# Sheet1.net
KiCad netlist of a schematic drawn in Altium Designer
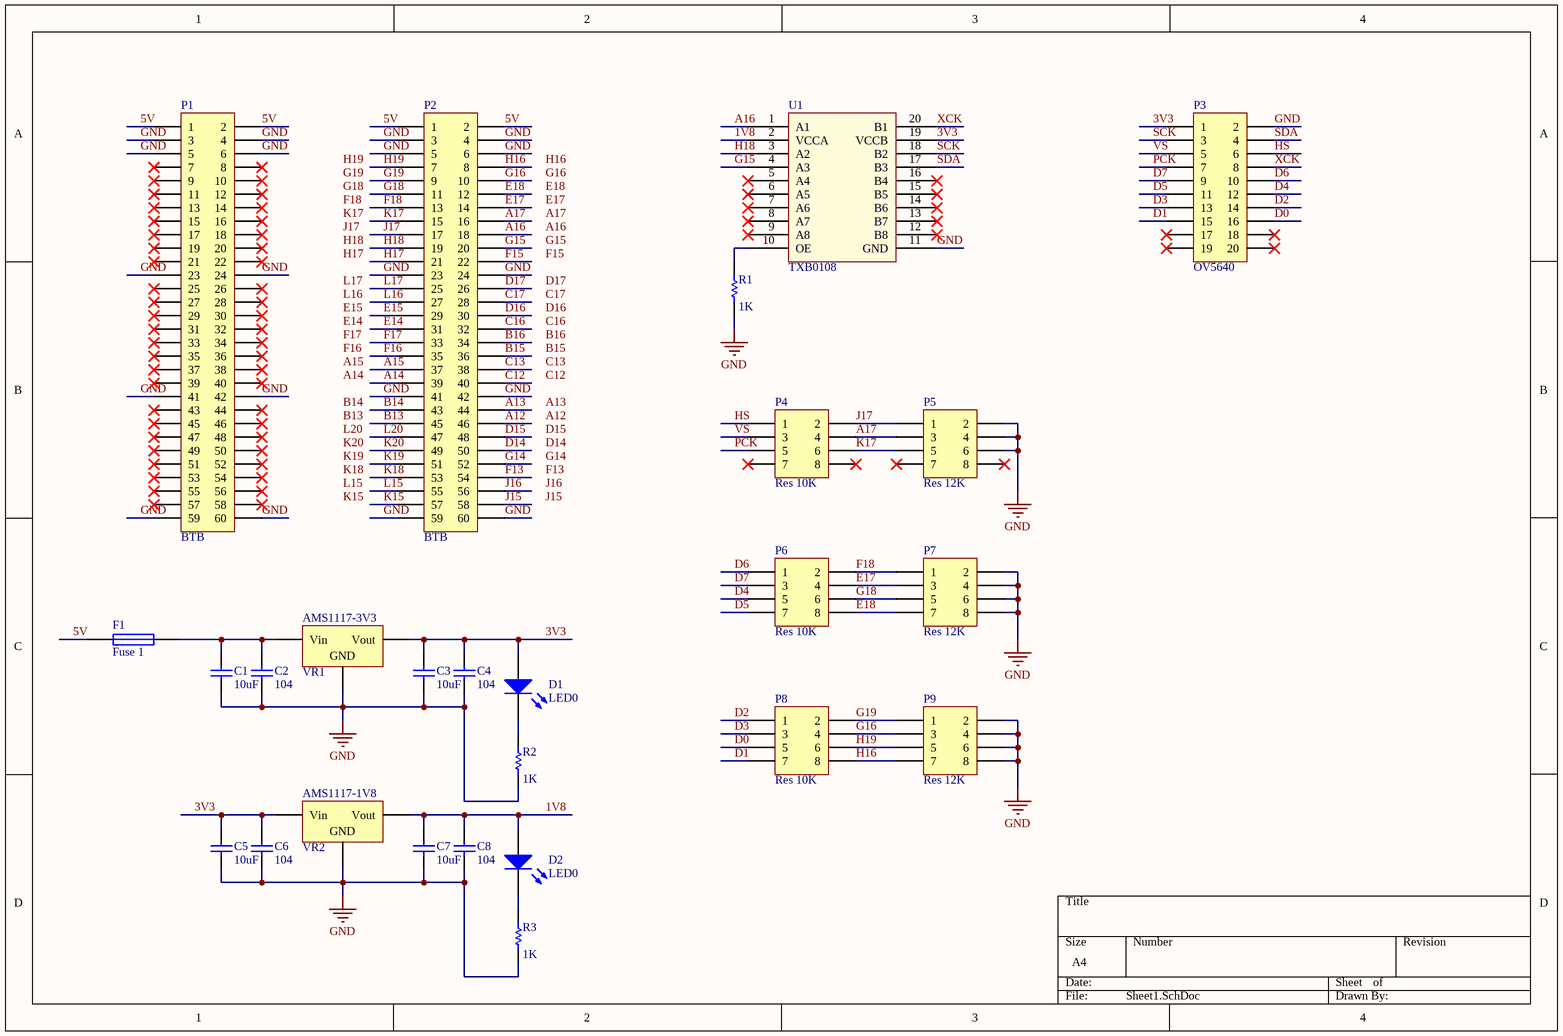
[diagram p0: Sheet1.SchDoc]

(export (version "E")
  (design (tool "Eeschema 10.0.6"))
  (components
    (comp (ref "C1")
      (value "10uF")
      (footprint "R0805")
      (description "Capacitor")
      (fields (field (name "Comment") "Cap") (field (name "PUBLISHER") "Altium Limited"))
      (libsource (lib "Miscellaneous Devices") (part "Cap"))
    )
    (comp (ref "C2")
      (value "104")
      (footprint "R0805")
      (description "Capacitor")
      (fields (field (name "Comment") "Cap") (field (name "PUBLISHER") "Altium Limited"))
      (libsource (lib "Miscellaneous Devices") (part "Cap"))
    )
    (comp (ref "C3")
      (value "10uF")
      (footprint "R0805")
      (description "Capacitor")
      (fields (field (name "Comment") "Cap") (field (name "PUBLISHER") "Altium Limited"))
      (libsource (lib "Miscellaneous Devices") (part "Cap"))
    )
    (comp (ref "C4")
      (value "104")
      (footprint "R0805")
      (description "Capacitor")
      (fields (field (name "Comment") "Cap") (field (name "PUBLISHER") "Altium Limited"))
      (libsource (lib "Miscellaneous Devices") (part "Cap"))
    )
    (comp (ref "C5")
      (value "10uF")
      (footprint "R0805")
      (description "Capacitor")
      (fields (field (name "Comment") "Cap") (field (name "PUBLISHER") "Altium Limited"))
      (libsource (lib "Miscellaneous Devices") (part "Cap"))
    )
    (comp (ref "C6")
      (value "104")
      (footprint "R0805")
      (description "Capacitor")
      (fields (field (name "Comment") "Cap") (field (name "PUBLISHER") "Altium Limited"))
      (libsource (lib "Miscellaneous Devices") (part "Cap"))
    )
    (comp (ref "C7")
      (value "10uF")
      (footprint "R0805")
      (description "Capacitor")
      (fields (field (name "Comment") "Cap") (field (name "PUBLISHER") "Altium Limited"))
      (libsource (lib "Miscellaneous Devices") (part "Cap"))
    )
    (comp (ref "C8")
      (value "104")
      (footprint "R0805")
      (description "Capacitor")
      (fields (field (name "Comment") "Cap") (field (name "PUBLISHER") "Altium Limited"))
      (libsource (lib "Miscellaneous Devices") (part "Cap"))
    )
    (comp (ref "D1")
      (value "LED0")
      (footprint "LED0805红")
      (description "Typical INFRARED GaAs LED")
      (fields (field (name "PUBLISHER") "Altium Limited"))
      (libsource (lib "Miscellaneous Devices") (part "LED0"))
    )
    (comp (ref "D2")
      (value "LED0")
      (footprint "LED0805红")
      (description "Typical INFRARED GaAs LED")
      (fields (field (name "PUBLISHER") "Altium Limited"))
      (libsource (lib "Miscellaneous Devices") (part "LED0"))
    )
    (comp (ref "F1")
      (value "Fuse 1")
      (footprint "R0805")
      (description "Fuse")
      (fields (field (name "PUBLISHER") "Altium Limited"))
      (libsource (lib "Miscellaneous Devices") (part "Fuse 1"))
    )
    (comp (ref "P1")
      (value "BTB")
      (footprint "BTBCON_0.8mm_60P")
      (description "Header, 30-Pin, Dual row")
      (fields (field (name "PUBLISHER") "Altium Limited"))
      (libsource (lib "Miscellaneous Connectors") (part "Header 30X2"))
    )
    (comp (ref "P2")
      (value "BTB")
      (footprint "BTBCON_0.8mm_60P")
      (description "Header, 30-Pin, Dual row")
      (fields (field (name "PUBLISHER") "Altium Limited"))
      (libsource (lib "Miscellaneous Connectors") (part "Header 30X2"))
    )
    (comp (ref "P3")
      (value "OV5640")
      (footprint "HDR2X10")
      (description "Header, 10-Pin, Dual row")
      (fields (field (name "PUBLISHER") "Altium Limited"))
      (libsource (lib "Miscellaneous Connectors") (part "Header 10X2"))
    )
    (comp (ref "P4")
      (value "Res 10K")
      (footprint "排阻(4位贴片)")
      (description "Header, 4-Pin, Dual row")
      (fields (field (name "PUBLISHER") "Altium Limited"))
      (libsource (lib "Miscellaneous Connectors") (part "Header 4X2"))
    )
    (comp (ref "P5")
      (value "Res 12K")
      (footprint "排阻(4位贴片)")
      (description "Header, 4-Pin, Dual row")
      (fields (field (name "PUBLISHER") "Altium Limited"))
      (libsource (lib "Miscellaneous Connectors") (part "Header 4X2"))
    )
    (comp (ref "P6")
      (value "Res 10K")
      (footprint "排阻(4位贴片)")
      (description "Header, 4-Pin, Dual row")
      (fields (field (name "PUBLISHER") "Altium Limited"))
      (libsource (lib "Miscellaneous Connectors") (part "Header 4X2"))
    )
    (comp (ref "P7")
      (value "Res 12K")
      (footprint "排阻(4位贴片)")
      (description "Header, 4-Pin, Dual row")
      (fields (field (name "PUBLISHER") "Altium Limited"))
      (libsource (lib "Miscellaneous Connectors") (part "Header 4X2"))
    )
    (comp (ref "P8")
      (value "Res 10K")
      (footprint "排阻(4位贴片)")
      (description "Header, 4-Pin, Dual row")
      (fields (field (name "PUBLISHER") "Altium Limited"))
      (libsource (lib "Miscellaneous Connectors") (part "Header 4X2"))
    )
    (comp (ref "P9")
      (value "Res 12K")
      (footprint "排阻(4位贴片)")
      (description "Header, 4-Pin, Dual row")
      (fields (field (name "PUBLISHER") "Altium Limited"))
      (libsource (lib "Miscellaneous Connectors") (part "Header 4X2"))
    )
    (comp (ref "R1")
      (value "1K")
      (footprint "R0805")
      (description "Semiconductor Resistor")
      (fields (field (name "Comment") "Res Semi") (field (name "PUBLISHER") "Altium Limited"))
      (libsource (lib "Miscellaneous Devices") (part "Res Semi"))
    )
    (comp (ref "R2")
      (value "1K")
      (footprint "R0805")
      (description "Resistor")
      (fields (field (name "Comment") "Res1") (field (name "PUBLISHER") "Altium Limited"))
      (libsource (lib "Miscellaneous Devices") (part "Res1"))
    )
    (comp (ref "R3")
      (value "1K")
      (footprint "R0805")
      (description "Resistor")
      (fields (field (name "Comment") "Res1") (field (name "PUBLISHER") "Altium Limited"))
      (libsource (lib "Miscellaneous Devices") (part "Res1"))
    )
    (comp (ref "U1") (value "TXB0108") (footprint "TXB0108") (libsource (lib "TXB0108") (part "TXB0108")))
    (comp (ref "VR1")
      (value "AMS1117-3V3")
      (footprint "AMS1117")
      (description "Voltage Regulator")
      (fields (field (name "PUBLISHER") "Altium Limited"))
      (libsource (lib "Miscellaneous Devices") (part "Volt Reg"))
    )
    (comp (ref "VR2")
      (value "AMS1117-1V8")
      (footprint "AMS1117")
      (description "Voltage Regulator")
      (fields (field (name "PUBLISHER") "Altium Limited"))
      (libsource (lib "Miscellaneous Devices") (part "Volt Reg"))
    )
  )
  (nets
    (net (code "1") (name "/1V8") (class "Default")
      (node (ref "C7") (pin "2") (pinfunction "2_2") (pintype "passive"))
      (node (ref "C8") (pin "2") (pinfunction "2_2") (pintype "passive"))
      (node (ref "D2") (pin "1") (pinfunction "A_1") (pintype "passive"))
      (node (ref "U1") (pin "2") (pinfunction "VCCA_2") (pintype "passive"))
      (node (ref "VR2") (pin "2") (pinfunction "Vout_2") (pintype "passive"))
    )
    (net (code "2") (name "/3V3") (class "Default")
      (node (ref "C3") (pin "2") (pinfunction "2_2") (pintype "passive"))
      (node (ref "C4") (pin "2") (pinfunction "2_2") (pintype "passive"))
      (node (ref "C5") (pin "2") (pinfunction "2_2") (pintype "passive"))
      (node (ref "C6") (pin "2") (pinfunction "2_2") (pintype "passive"))
      (node (ref "D1") (pin "1") (pinfunction "A_1") (pintype "passive"))
      (node (ref "P3") (pin "1") (pinfunction "1_1") (pintype "passive"))
      (node (ref "U1") (pin "19") (pinfunction "VCCB_19") (pintype "passive"))
      (node (ref "VR1") (pin "2") (pinfunction "Vout_2") (pintype "passive"))
      (node (ref "VR2") (pin "3") (pinfunction "Vin_3") (pintype "passive"))
    )
    (net (code "3") (name "/5V") (class "Default")
      (node (ref "F1") (pin "1") (pinfunction "1_1") (pintype "passive"))
      (node (ref "P1") (pin "1") (pinfunction "1_1") (pintype "passive"))
      (node (ref "P1") (pin "2") (pinfunction "2_2") (pintype "passive"))
      (node (ref "P2") (pin "1") (pinfunction "1_1") (pintype "passive"))
      (node (ref "P2") (pin "2") (pinfunction "2_2") (pintype "passive"))
    )
    (net (code "4") (name "/A12") (class "Default")
      (node (ref "P2") (pin "46") (pinfunction "46_46") (pintype "passive"))
    )
    (net (code "5") (name "/A13") (class "Default")
      (node (ref "P2") (pin "44") (pinfunction "44_44") (pintype "passive"))
    )
    (net (code "6") (name "/A14") (class "Default")
      (node (ref "P2") (pin "39") (pinfunction "39_39") (pintype "passive"))
    )
    (net (code "7") (name "/A15") (class "Default")
      (node (ref "P2") (pin "37") (pinfunction "37_37") (pintype "passive"))
    )
    (net (code "8") (name "/A16") (class "Default")
      (node (ref "P2") (pin "18") (pinfunction "18_18") (pintype "passive"))
      (node (ref "U1") (pin "1") (pinfunction "A1_1") (pintype "passive"))
    )
    (net (code "9") (name "/A17") (class "Default")
      (node (ref "P2") (pin "16") (pinfunction "16_16") (pintype "passive"))
      (node (ref "P4") (pin "4") (pinfunction "4_4") (pintype "passive"))
      (node (ref "P5") (pin "3") (pinfunction "3_3") (pintype "passive"))
    )
    (net (code "10") (name "/B13") (class "Default")
      (node (ref "P2") (pin "45") (pinfunction "45_45") (pintype "passive"))
    )
    (net (code "11") (name "/B14") (class "Default")
      (node (ref "P2") (pin "43") (pinfunction "43_43") (pintype "passive"))
    )
    (net (code "12") (name "/B15") (class "Default")
      (node (ref "P2") (pin "36") (pinfunction "36_36") (pintype "passive"))
    )
    (net (code "13") (name "/B16") (class "Default")
      (node (ref "P2") (pin "34") (pinfunction "34_34") (pintype "passive"))
    )
    (net (code "14") (name "/C12") (class "Default")
      (node (ref "P2") (pin "40") (pinfunction "40_40") (pintype "passive"))
    )
    (net (code "15") (name "/C13") (class "Default")
      (node (ref "P2") (pin "38") (pinfunction "38_38") (pintype "passive"))
    )
    (net (code "16") (name "/C16") (class "Default")
      (node (ref "P2") (pin "32") (pinfunction "32_32") (pintype "passive"))
    )
    (net (code "17") (name "/C17") (class "Default")
      (node (ref "P2") (pin "28") (pinfunction "28_28") (pintype "passive"))
    )
    (net (code "18") (name "/D0") (class "Default")
      (node (ref "P3") (pin "16") (pinfunction "16_16") (pintype "passive"))
      (node (ref "P8") (pin "5") (pinfunction "5_5") (pintype "passive"))
    )
    (net (code "19") (name "/D1") (class "Default")
      (node (ref "P3") (pin "15") (pinfunction "15_15") (pintype "passive"))
      (node (ref "P8") (pin "7") (pinfunction "7_7") (pintype "passive"))
    )
    (net (code "20") (name "/D2") (class "Default")
      (node (ref "P3") (pin "14") (pinfunction "14_14") (pintype "passive"))
      (node (ref "P8") (pin "1") (pinfunction "1_1") (pintype "passive"))
    )
    (net (code "21") (name "/D3") (class "Default")
      (node (ref "P3") (pin "13") (pinfunction "13_13") (pintype "passive"))
      (node (ref "P8") (pin "3") (pinfunction "3_3") (pintype "passive"))
    )
    (net (code "22") (name "/D4") (class "Default")
      (node (ref "P3") (pin "12") (pinfunction "12_12") (pintype "passive"))
      (node (ref "P6") (pin "5") (pinfunction "5_5") (pintype "passive"))
    )
    (net (code "23") (name "/D5") (class "Default")
      (node (ref "P3") (pin "11") (pinfunction "11_11") (pintype "passive"))
      (node (ref "P6") (pin "7") (pinfunction "7_7") (pintype "passive"))
    )
    (net (code "24") (name "/D6") (class "Default")
      (node (ref "P3") (pin "10") (pinfunction "10_10") (pintype "passive"))
      (node (ref "P6") (pin "1") (pinfunction "1_1") (pintype "passive"))
    )
    (net (code "25") (name "/D7") (class "Default")
      (node (ref "P3") (pin "9") (pinfunction "9_9") (pintype "passive"))
      (node (ref "P6") (pin "3") (pinfunction "3_3") (pintype "passive"))
    )
    (net (code "26") (name "/D14") (class "Default")
      (node (ref "P2") (pin "50") (pinfunction "50_50") (pintype "passive"))
    )
    (net (code "27") (name "/D15") (class "Default")
      (node (ref "P2") (pin "48") (pinfunction "48_48") (pintype "passive"))
    )
    (net (code "28") (name "/D16") (class "Default")
      (node (ref "P2") (pin "30") (pinfunction "30_30") (pintype "passive"))
    )
    (net (code "29") (name "/D17") (class "Default")
      (node (ref "P2") (pin "26") (pinfunction "26_26") (pintype "passive"))
    )
    (net (code "30") (name "/E14") (class "Default")
      (node (ref "P2") (pin "31") (pinfunction "31_31") (pintype "passive"))
    )
    (net (code "31") (name "/E15") (class "Default")
      (node (ref "P2") (pin "29") (pinfunction "29_29") (pintype "passive"))
    )
    (net (code "32") (name "/E17") (class "Default")
      (node (ref "P2") (pin "14") (pinfunction "14_14") (pintype "passive"))
      (node (ref "P6") (pin "4") (pinfunction "4_4") (pintype "passive"))
      (node (ref "P7") (pin "3") (pinfunction "3_3") (pintype "passive"))
    )
    (net (code "33") (name "/E18") (class "Default")
      (node (ref "P2") (pin "12") (pinfunction "12_12") (pintype "passive"))
      (node (ref "P6") (pin "8") (pinfunction "8_8") (pintype "passive"))
      (node (ref "P7") (pin "7") (pinfunction "7_7") (pintype "passive"))
    )
    (net (code "34") (name "/F13") (class "Default")
      (node (ref "P2") (pin "54") (pinfunction "54_54") (pintype "passive"))
    )
    (net (code "35") (name "/F15") (class "Default")
      (node (ref "P2") (pin "22") (pinfunction "22_22") (pintype "passive"))
    )
    (net (code "36") (name "/F16") (class "Default")
      (node (ref "P2") (pin "35") (pinfunction "35_35") (pintype "passive"))
    )
    (net (code "37") (name "/F17") (class "Default")
      (node (ref "P2") (pin "33") (pinfunction "33_33") (pintype "passive"))
    )
    (net (code "38") (name "/F18") (class "Default")
      (node (ref "P2") (pin "13") (pinfunction "13_13") (pintype "passive"))
      (node (ref "P6") (pin "2") (pinfunction "2_2") (pintype "passive"))
      (node (ref "P7") (pin "1") (pinfunction "1_1") (pintype "passive"))
    )
    (net (code "39") (name "/G14") (class "Default")
      (node (ref "P2") (pin "52") (pinfunction "52_52") (pintype "passive"))
    )
    (net (code "40") (name "/G15") (class "Default")
      (node (ref "P2") (pin "20") (pinfunction "20_20") (pintype "passive"))
      (node (ref "U1") (pin "4") (pinfunction "A3_4") (pintype "passive"))
    )
    (net (code "41") (name "/G16") (class "Default")
      (node (ref "P2") (pin "10") (pinfunction "10_10") (pintype "passive"))
      (node (ref "P8") (pin "4") (pinfunction "4_4") (pintype "passive"))
      (node (ref "P9") (pin "3") (pinfunction "3_3") (pintype "passive"))
    )
    (net (code "42") (name "/G18") (class "Default")
      (node (ref "P2") (pin "11") (pinfunction "11_11") (pintype "passive"))
      (node (ref "P6") (pin "6") (pinfunction "6_6") (pintype "passive"))
      (node (ref "P7") (pin "5") (pinfunction "5_5") (pintype "passive"))
    )
    (net (code "43") (name "/G19") (class "Default")
      (node (ref "P2") (pin "9") (pinfunction "9_9") (pintype "passive"))
      (node (ref "P8") (pin "2") (pinfunction "2_2") (pintype "passive"))
      (node (ref "P9") (pin "1") (pinfunction "1_1") (pintype "passive"))
    )
    (net (code "44") (name "/H16") (class "Default")
      (node (ref "P2") (pin "8") (pinfunction "8_8") (pintype "passive"))
      (node (ref "P8") (pin "8") (pinfunction "8_8") (pintype "passive"))
      (node (ref "P9") (pin "7") (pinfunction "7_7") (pintype "passive"))
    )
    (net (code "45") (name "/H17") (class "Default")
      (node (ref "P2") (pin "21") (pinfunction "21_21") (pintype "passive"))
    )
    (net (code "46") (name "/H18") (class "Default")
      (node (ref "P2") (pin "19") (pinfunction "19_19") (pintype "passive"))
      (node (ref "U1") (pin "3") (pinfunction "A2_3") (pintype "passive"))
    )
    (net (code "47") (name "/H19") (class "Default")
      (node (ref "P2") (pin "7") (pinfunction "7_7") (pintype "passive"))
      (node (ref "P8") (pin "6") (pinfunction "6_6") (pintype "passive"))
      (node (ref "P9") (pin "5") (pinfunction "5_5") (pintype "passive"))
    )
    (net (code "48") (name "/HS") (class "Default")
      (node (ref "P3") (pin "6") (pinfunction "6_6") (pintype "passive"))
      (node (ref "P4") (pin "1") (pinfunction "1_1") (pintype "passive"))
    )
    (net (code "49") (name "/J15") (class "Default")
      (node (ref "P2") (pin "58") (pinfunction "58_58") (pintype "passive"))
    )
    (net (code "50") (name "/J16") (class "Default")
      (node (ref "P2") (pin "56") (pinfunction "56_56") (pintype "passive"))
    )
    (net (code "51") (name "/J17") (class "Default")
      (node (ref "P2") (pin "17") (pinfunction "17_17") (pintype "passive"))
      (node (ref "P4") (pin "2") (pinfunction "2_2") (pintype "passive"))
      (node (ref "P5") (pin "1") (pinfunction "1_1") (pintype "passive"))
    )
    (net (code "52") (name "/K15") (class "Default")
      (node (ref "P2") (pin "57") (pinfunction "57_57") (pintype "passive"))
    )
    (net (code "53") (name "/K17") (class "Default")
      (node (ref "P2") (pin "15") (pinfunction "15_15") (pintype "passive"))
      (node (ref "P4") (pin "6") (pinfunction "6_6") (pintype "passive"))
      (node (ref "P5") (pin "5") (pinfunction "5_5") (pintype "passive"))
    )
    (net (code "54") (name "/K18") (class "Default")
      (node (ref "P2") (pin "53") (pinfunction "53_53") (pintype "passive"))
    )
    (net (code "55") (name "/K19") (class "Default")
      (node (ref "P2") (pin "51") (pinfunction "51_51") (pintype "passive"))
    )
    (net (code "56") (name "/K20") (class "Default")
      (node (ref "P2") (pin "49") (pinfunction "49_49") (pintype "passive"))
    )
    (net (code "57") (name "/L15") (class "Default")
      (node (ref "P2") (pin "55") (pinfunction "55_55") (pintype "passive"))
    )
    (net (code "58") (name "/L16") (class "Default")
      (node (ref "P2") (pin "27") (pinfunction "27_27") (pintype "passive"))
    )
    (net (code "59") (name "/L17") (class "Default")
      (node (ref "P2") (pin "25") (pinfunction "25_25") (pintype "passive"))
    )
    (net (code "60") (name "/L20") (class "Default")
      (node (ref "P2") (pin "47") (pinfunction "47_47") (pintype "passive"))
    )
    (net (code "61") (name "/PCK") (class "Default")
      (node (ref "P3") (pin "7") (pinfunction "7_7") (pintype "passive"))
      (node (ref "P4") (pin "5") (pinfunction "5_5") (pintype "passive"))
    )
    (net (code "62") (name "/SCK") (class "Default")
      (node (ref "P3") (pin "3") (pinfunction "3_3") (pintype "passive"))
      (node (ref "U1") (pin "18") (pinfunction "B2_18") (pintype "passive"))
    )
    (net (code "63") (name "/SDA") (class "Default")
      (node (ref "P3") (pin "4") (pinfunction "4_4") (pintype "passive"))
      (node (ref "U1") (pin "17") (pinfunction "B3_17") (pintype "passive"))
    )
    (net (code "64") (name "/VS") (class "Default")
      (node (ref "P3") (pin "5") (pinfunction "5_5") (pintype "passive"))
      (node (ref "P4") (pin "3") (pinfunction "3_3") (pintype "passive"))
    )
    (net (code "65") (name "/XCK") (class "Default")
      (node (ref "P3") (pin "8") (pinfunction "8_8") (pintype "passive"))
      (node (ref "U1") (pin "20") (pinfunction "B1_20") (pintype "passive"))
    )
    (net (code "66") (name "GND") (class "Default")
      (node (ref "C1") (pin "1") (pinfunction "1_1") (pintype "passive"))
      (node (ref "C2") (pin "1") (pinfunction "1_1") (pintype "passive"))
      (node (ref "C3") (pin "1") (pinfunction "1_1") (pintype "passive"))
      (node (ref "C4") (pin "1") (pinfunction "1_1") (pintype "passive"))
      (node (ref "C5") (pin "1") (pinfunction "1_1") (pintype "passive"))
      (node (ref "C6") (pin "1") (pinfunction "1_1") (pintype "passive"))
      (node (ref "C7") (pin "1") (pinfunction "1_1") (pintype "passive"))
      (node (ref "C8") (pin "1") (pinfunction "1_1") (pintype "passive"))
      (node (ref "P1") (pin "23") (pinfunction "23_23") (pintype "passive"))
      (node (ref "P1") (pin "24") (pinfunction "24_24") (pintype "passive"))
      (node (ref "P1") (pin "3") (pinfunction "3_3") (pintype "passive"))
      (node (ref "P1") (pin "4") (pinfunction "4_4") (pintype "passive"))
      (node (ref "P1") (pin "41") (pinfunction "41_41") (pintype "passive"))
      (node (ref "P1") (pin "42") (pinfunction "42_42") (pintype "passive"))
      (node (ref "P1") (pin "5") (pinfunction "5_5") (pintype "passive"))
      (node (ref "P1") (pin "59") (pinfunction "59_59") (pintype "passive"))
      (node (ref "P1") (pin "6") (pinfunction "6_6") (pintype "passive"))
      (node (ref "P1") (pin "60") (pinfunction "60_60") (pintype "passive"))
      (node (ref "P2") (pin "23") (pinfunction "23_23") (pintype "passive"))
      (node (ref "P2") (pin "24") (pinfunction "24_24") (pintype "passive"))
      (node (ref "P2") (pin "3") (pinfunction "3_3") (pintype "passive"))
      (node (ref "P2") (pin "4") (pinfunction "4_4") (pintype "passive"))
      (node (ref "P2") (pin "41") (pinfunction "41_41") (pintype "passive"))
      (node (ref "P2") (pin "42") (pinfunction "42_42") (pintype "passive"))
      (node (ref "P2") (pin "5") (pinfunction "5_5") (pintype "passive"))
      (node (ref "P2") (pin "59") (pinfunction "59_59") (pintype "passive"))
      (node (ref "P2") (pin "6") (pinfunction "6_6") (pintype "passive"))
      (node (ref "P2") (pin "60") (pinfunction "60_60") (pintype "passive"))
      (node (ref "P3") (pin "2") (pinfunction "2_2") (pintype "passive"))
      (node (ref "P5") (pin "2") (pinfunction "2_2") (pintype "passive"))
      (node (ref "P5") (pin "4") (pinfunction "4_4") (pintype "passive"))
      (node (ref "P5") (pin "6") (pinfunction "6_6") (pintype "passive"))
      (node (ref "P7") (pin "2") (pinfunction "2_2") (pintype "passive"))
      (node (ref "P7") (pin "4") (pinfunction "4_4") (pintype "passive"))
      (node (ref "P7") (pin "6") (pinfunction "6_6") (pintype "passive"))
      (node (ref "P7") (pin "8") (pinfunction "8_8") (pintype "passive"))
      (node (ref "P9") (pin "2") (pinfunction "2_2") (pintype "passive"))
      (node (ref "P9") (pin "4") (pinfunction "4_4") (pintype "passive"))
      (node (ref "P9") (pin "6") (pinfunction "6_6") (pintype "passive"))
      (node (ref "P9") (pin "8") (pinfunction "8_8") (pintype "passive"))
      (node (ref "R1") (pin "1") (pinfunction "1_1") (pintype "passive"))
      (node (ref "R2") (pin "1") (pinfunction "1_1") (pintype "passive"))
      (node (ref "R3") (pin "1") (pinfunction "1_1") (pintype "passive"))
      (node (ref "U1") (pin "11") (pinfunction "GND_11") (pintype "passive"))
      (node (ref "VR1") (pin "1") (pinfunction "GND_1") (pintype "passive"))
      (node (ref "VR2") (pin "1") (pinfunction "GND_1") (pintype "passive"))
    )
    (net (code "67") (name "Net-(D1-K)") (class "Default")
      (node (ref "D1") (pin "2") (pinfunction "K_2") (pintype "passive"))
      (node (ref "R2") (pin "2") (pinfunction "2_2") (pintype "passive"))
    )
    (net (code "68") (name "Net-(D2-K)") (class "Default")
      (node (ref "D2") (pin "2") (pinfunction "K_2") (pintype "passive"))
      (node (ref "R3") (pin "2") (pinfunction "2_2") (pintype "passive"))
    )
    (net (code "69") (name "Net-(U1-OE)") (class "Default")
      (node (ref "R1") (pin "2") (pinfunction "2_2") (pintype "passive"))
      (node (ref "U1") (pin "10") (pinfunction "OE_10") (pintype "passive"))
    )
    (net (code "70") (name "Net-(VR1-Vin)") (class "Default")
      (node (ref "C1") (pin "2") (pinfunction "2_2") (pintype "passive"))
      (node (ref "C2") (pin "2") (pinfunction "2_2") (pintype "passive"))
      (node (ref "F1") (pin "2") (pinfunction "2_2") (pintype "passive"))
      (node (ref "VR1") (pin "3") (pinfunction "Vin_3") (pintype "passive"))
    )
    (net (code "71") (name "unconnected-(P1-Pad7)") (class "Default")
      (node (ref "P1") (pin "7") (pinfunction "7_7") (pintype "passive+no_connect"))
    )
    (net (code "72") (name "unconnected-(P1-Pad8)") (class "Default")
      (node (ref "P1") (pin "8") (pinfunction "8_8") (pintype "passive+no_connect"))
    )
    (net (code "73") (name "unconnected-(P1-Pad9)") (class "Default")
      (node (ref "P1") (pin "9") (pinfunction "9_9") (pintype "passive+no_connect"))
    )
    (net (code "74") (name "unconnected-(P1-Pad10)") (class "Default")
      (node (ref "P1") (pin "10") (pinfunction "10_10") (pintype "passive+no_connect"))
    )
    (net (code "75") (name "unconnected-(P1-Pad11)") (class "Default")
      (node (ref "P1") (pin "11") (pinfunction "11_11") (pintype "passive+no_connect"))
    )
    (net (code "76") (name "unconnected-(P1-Pad12)") (class "Default")
      (node (ref "P1") (pin "12") (pinfunction "12_12") (pintype "passive+no_connect"))
    )
    (net (code "77") (name "unconnected-(P1-Pad13)") (class "Default")
      (node (ref "P1") (pin "13") (pinfunction "13_13") (pintype "passive+no_connect"))
    )
    (net (code "78") (name "unconnected-(P1-Pad14)") (class "Default")
      (node (ref "P1") (pin "14") (pinfunction "14_14") (pintype "passive+no_connect"))
    )
    (net (code "79") (name "unconnected-(P1-Pad15)") (class "Default")
      (node (ref "P1") (pin "15") (pinfunction "15_15") (pintype "passive+no_connect"))
    )
    (net (code "80") (name "unconnected-(P1-Pad16)") (class "Default")
      (node (ref "P1") (pin "16") (pinfunction "16_16") (pintype "passive+no_connect"))
    )
    (net (code "81") (name "unconnected-(P1-Pad17)") (class "Default")
      (node (ref "P1") (pin "17") (pinfunction "17_17") (pintype "passive+no_connect"))
    )
    (net (code "82") (name "unconnected-(P1-Pad18)") (class "Default")
      (node (ref "P1") (pin "18") (pinfunction "18_18") (pintype "passive+no_connect"))
    )
    (net (code "83") (name "unconnected-(P1-Pad19)") (class "Default")
      (node (ref "P1") (pin "19") (pinfunction "19_19") (pintype "passive+no_connect"))
    )
    (net (code "84") (name "unconnected-(P1-Pad20)") (class "Default")
      (node (ref "P1") (pin "20") (pinfunction "20_20") (pintype "passive+no_connect"))
    )
    (net (code "85") (name "unconnected-(P1-Pad21)") (class "Default")
      (node (ref "P1") (pin "21") (pinfunction "21_21") (pintype "passive+no_connect"))
    )
    (net (code "86") (name "unconnected-(P1-Pad22)") (class "Default")
      (node (ref "P1") (pin "22") (pinfunction "22_22") (pintype "passive+no_connect"))
    )
    (net (code "87") (name "unconnected-(P1-Pad25)") (class "Default")
      (node (ref "P1") (pin "25") (pinfunction "25_25") (pintype "passive+no_connect"))
    )
    (net (code "88") (name "unconnected-(P1-Pad26)") (class "Default")
      (node (ref "P1") (pin "26") (pinfunction "26_26") (pintype "passive+no_connect"))
    )
    (net (code "89") (name "unconnected-(P1-Pad27)") (class "Default")
      (node (ref "P1") (pin "27") (pinfunction "27_27") (pintype "passive+no_connect"))
    )
    (net (code "90") (name "unconnected-(P1-Pad28)") (class "Default")
      (node (ref "P1") (pin "28") (pinfunction "28_28") (pintype "passive+no_connect"))
    )
    (net (code "91") (name "unconnected-(P1-Pad29)") (class "Default")
      (node (ref "P1") (pin "29") (pinfunction "29_29") (pintype "passive+no_connect"))
    )
    (net (code "92") (name "unconnected-(P1-Pad30)") (class "Default")
      (node (ref "P1") (pin "30") (pinfunction "30_30") (pintype "passive+no_connect"))
    )
    (net (code "93") (name "unconnected-(P1-Pad31)") (class "Default")
      (node (ref "P1") (pin "31") (pinfunction "31_31") (pintype "passive+no_connect"))
    )
    (net (code "94") (name "unconnected-(P1-Pad32)") (class "Default")
      (node (ref "P1") (pin "32") (pinfunction "32_32") (pintype "passive+no_connect"))
    )
    (net (code "95") (name "unconnected-(P1-Pad33)") (class "Default")
      (node (ref "P1") (pin "33") (pinfunction "33_33") (pintype "passive+no_connect"))
    )
    (net (code "96") (name "unconnected-(P1-Pad34)") (class "Default")
      (node (ref "P1") (pin "34") (pinfunction "34_34") (pintype "passive+no_connect"))
    )
    (net (code "97") (name "unconnected-(P1-Pad35)") (class "Default")
      (node (ref "P1") (pin "35") (pinfunction "35_35") (pintype "passive+no_connect"))
    )
    (net (code "98") (name "unconnected-(P1-Pad36)") (class "Default")
      (node (ref "P1") (pin "36") (pinfunction "36_36") (pintype "passive+no_connect"))
    )
    (net (code "99") (name "unconnected-(P1-Pad37)") (class "Default")
      (node (ref "P1") (pin "37") (pinfunction "37_37") (pintype "passive+no_connect"))
    )
    (net (code "100") (name "unconnected-(P1-Pad38)") (class "Default")
      (node (ref "P1") (pin "38") (pinfunction "38_38") (pintype "passive+no_connect"))
    )
    (net (code "101") (name "unconnected-(P1-Pad39)") (class "Default")
      (node (ref "P1") (pin "39") (pinfunction "39_39") (pintype "passive+no_connect"))
    )
    (net (code "102") (name "unconnected-(P1-Pad40)") (class "Default")
      (node (ref "P1") (pin "40") (pinfunction "40_40") (pintype "passive+no_connect"))
    )
    (net (code "103") (name "unconnected-(P1-Pad43)") (class "Default")
      (node (ref "P1") (pin "43") (pinfunction "43_43") (pintype "passive+no_connect"))
    )
    (net (code "104") (name "unconnected-(P1-Pad44)") (class "Default")
      (node (ref "P1") (pin "44") (pinfunction "44_44") (pintype "passive+no_connect"))
    )
    (net (code "105") (name "unconnected-(P1-Pad45)") (class "Default")
      (node (ref "P1") (pin "45") (pinfunction "45_45") (pintype "passive+no_connect"))
    )
    (net (code "106") (name "unconnected-(P1-Pad46)") (class "Default")
      (node (ref "P1") (pin "46") (pinfunction "46_46") (pintype "passive+no_connect"))
    )
    (net (code "107") (name "unconnected-(P1-Pad47)") (class "Default")
      (node (ref "P1") (pin "47") (pinfunction "47_47") (pintype "passive+no_connect"))
    )
    (net (code "108") (name "unconnected-(P1-Pad48)") (class "Default")
      (node (ref "P1") (pin "48") (pinfunction "48_48") (pintype "passive+no_connect"))
    )
    (net (code "109") (name "unconnected-(P1-Pad49)") (class "Default")
      (node (ref "P1") (pin "49") (pinfunction "49_49") (pintype "passive+no_connect"))
    )
    (net (code "110") (name "unconnected-(P1-Pad50)") (class "Default")
      (node (ref "P1") (pin "50") (pinfunction "50_50") (pintype "passive+no_connect"))
    )
    (net (code "111") (name "unconnected-(P1-Pad51)") (class "Default")
      (node (ref "P1") (pin "51") (pinfunction "51_51") (pintype "passive+no_connect"))
    )
    (net (code "112") (name "unconnected-(P1-Pad52)") (class "Default")
      (node (ref "P1") (pin "52") (pinfunction "52_52") (pintype "passive+no_connect"))
    )
    (net (code "113") (name "unconnected-(P1-Pad53)") (class "Default")
      (node (ref "P1") (pin "53") (pinfunction "53_53") (pintype "passive+no_connect"))
    )
    (net (code "114") (name "unconnected-(P1-Pad54)") (class "Default")
      (node (ref "P1") (pin "54") (pinfunction "54_54") (pintype "passive+no_connect"))
    )
    (net (code "115") (name "unconnected-(P1-Pad55)") (class "Default")
      (node (ref "P1") (pin "55") (pinfunction "55_55") (pintype "passive+no_connect"))
    )
    (net (code "116") (name "unconnected-(P1-Pad56)") (class "Default")
      (node (ref "P1") (pin "56") (pinfunction "56_56") (pintype "passive+no_connect"))
    )
    (net (code "117") (name "unconnected-(P1-Pad57)") (class "Default")
      (node (ref "P1") (pin "57") (pinfunction "57_57") (pintype "passive+no_connect"))
    )
    (net (code "118") (name "unconnected-(P1-Pad58)") (class "Default")
      (node (ref "P1") (pin "58") (pinfunction "58_58") (pintype "passive+no_connect"))
    )
    (net (code "119") (name "unconnected-(P3-Pad17)") (class "Default")
      (node (ref "P3") (pin "17") (pinfunction "17_17") (pintype "passive+no_connect"))
    )
    (net (code "120") (name "unconnected-(P3-Pad18)") (class "Default")
      (node (ref "P3") (pin "18") (pinfunction "18_18") (pintype "passive+no_connect"))
    )
    (net (code "121") (name "unconnected-(P3-Pad19)") (class "Default")
      (node (ref "P3") (pin "19") (pinfunction "19_19") (pintype "passive+no_connect"))
    )
    (net (code "122") (name "unconnected-(P3-Pad20)") (class "Default")
      (node (ref "P3") (pin "20") (pinfunction "20_20") (pintype "passive+no_connect"))
    )
    (net (code "123") (name "unconnected-(P4-Pad7)") (class "Default")
      (node (ref "P4") (pin "7") (pinfunction "7_7") (pintype "passive+no_connect"))
    )
    (net (code "124") (name "unconnected-(P4-Pad8)") (class "Default")
      (node (ref "P4") (pin "8") (pinfunction "8_8") (pintype "passive+no_connect"))
    )
    (net (code "125") (name "unconnected-(P5-Pad7)") (class "Default")
      (node (ref "P5") (pin "7") (pinfunction "7_7") (pintype "passive+no_connect"))
    )
    (net (code "126") (name "unconnected-(P5-Pad8)") (class "Default")
      (node (ref "P5") (pin "8") (pinfunction "8_8") (pintype "passive+no_connect"))
    )
    (net (code "127") (name "unconnected-(U1-A4-Pad5)") (class "Default")
      (node (ref "U1") (pin "5") (pinfunction "A4_5") (pintype "passive+no_connect"))
    )
    (net (code "128") (name "unconnected-(U1-A5-Pad6)") (class "Default")
      (node (ref "U1") (pin "6") (pinfunction "A5_6") (pintype "passive+no_connect"))
    )
    (net (code "129") (name "unconnected-(U1-A6-Pad7)") (class "Default")
      (node (ref "U1") (pin "7") (pinfunction "A6_7") (pintype "passive+no_connect"))
    )
    (net (code "130") (name "unconnected-(U1-A7-Pad8)") (class "Default")
      (node (ref "U1") (pin "8") (pinfunction "A7_8") (pintype "passive+no_connect"))
    )
    (net (code "131") (name "unconnected-(U1-A8-Pad9)") (class "Default")
      (node (ref "U1") (pin "9") (pinfunction "A8_9") (pintype "passive+no_connect"))
    )
    (net (code "132") (name "unconnected-(U1-B4-Pad16)") (class "Default")
      (node (ref "U1") (pin "16") (pinfunction "B4_16") (pintype "passive+no_connect"))
    )
    (net (code "133") (name "unconnected-(U1-B5-Pad15)") (class "Default")
      (node (ref "U1") (pin "15") (pinfunction "B5_15") (pintype "passive+no_connect"))
    )
    (net (code "134") (name "unconnected-(U1-B6-Pad14)") (class "Default")
      (node (ref "U1") (pin "14") (pinfunction "B6_14") (pintype "passive+no_connect"))
    )
    (net (code "135") (name "unconnected-(U1-B7-Pad13)") (class "Default")
      (node (ref "U1") (pin "13") (pinfunction "B7_13") (pintype "passive+no_connect"))
    )
    (net (code "136") (name "unconnected-(U1-B8-Pad12)") (class "Default")
      (node (ref "U1") (pin "12") (pinfunction "B8_12") (pintype "passive+no_connect"))
    )
  )
)
